# dualsmartplug.net
KiCad netlist of a schematic drawn in EAGLE
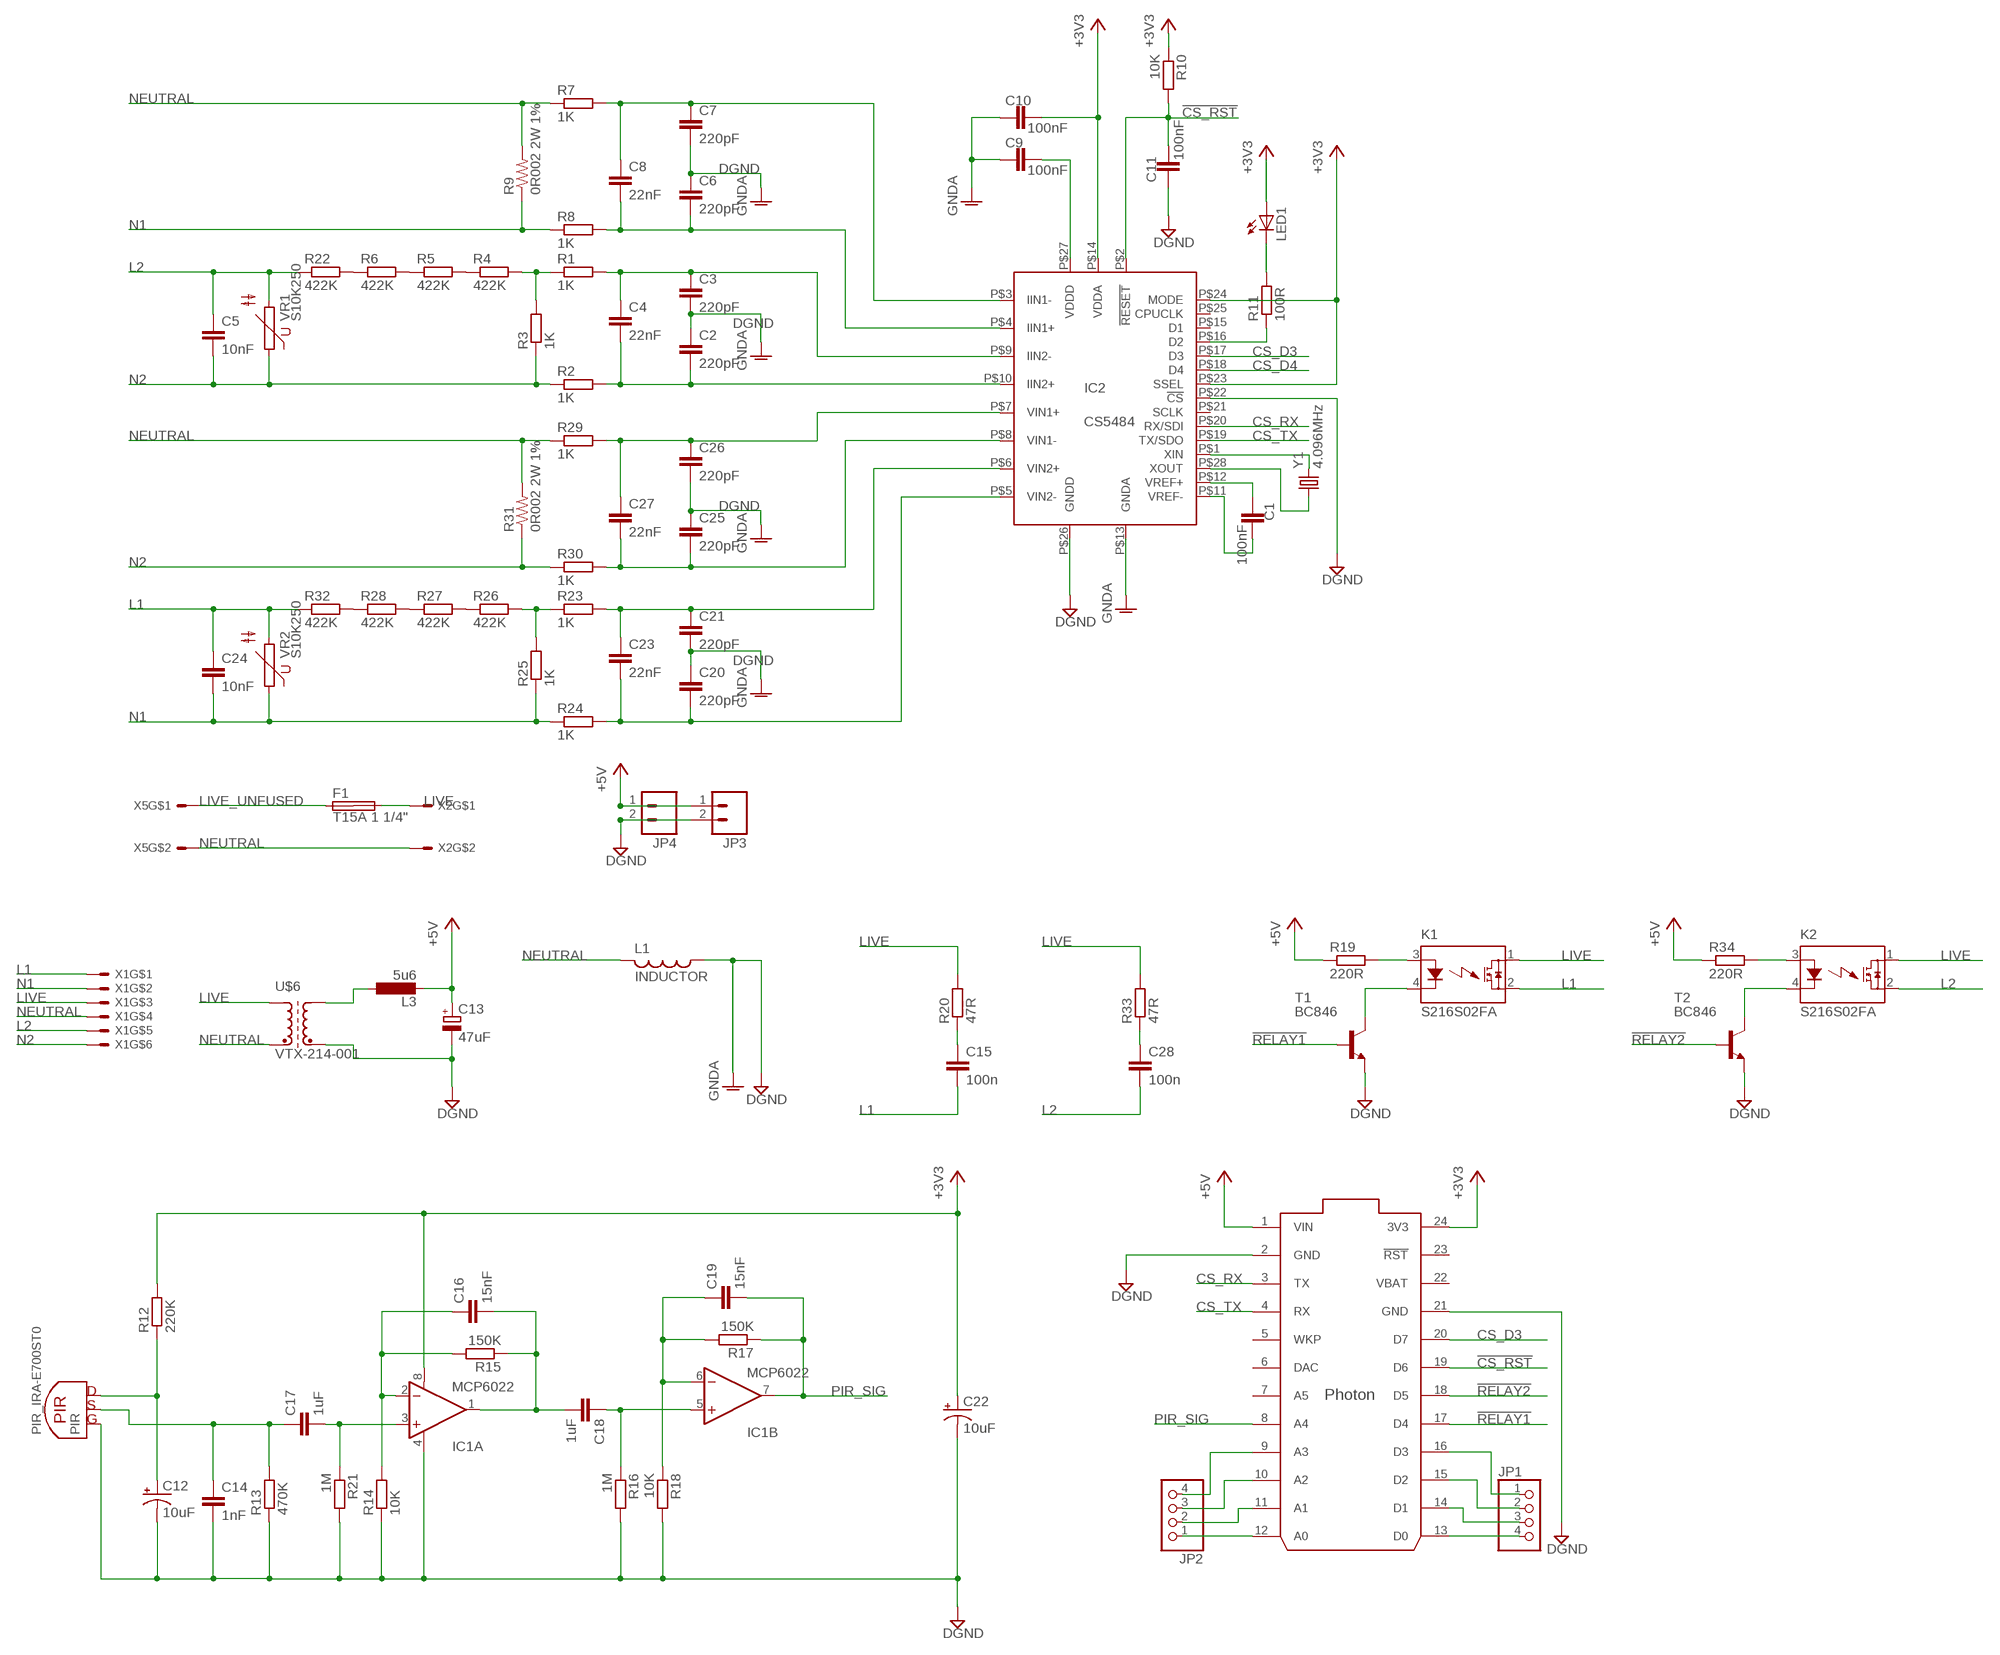
[diagram p0: schematic, sheet 1]

(export (version "E")
  (design (tool "Eeschema 10.0.6"))
  (components
    (comp (ref "C1")
      (value "100nF")
      (footprint "eagle-import:0603-CAP")
      (libsource (lib "eagle-import") (part "CAP0603-CAP"))
    )
    (comp (ref "C2")
      (value "220pF")
      (footprint "eagle-import:0603-CAP")
      (libsource (lib "eagle-import") (part "CAP0603-CAP"))
    )
    (comp (ref "C3")
      (value "220pF")
      (footprint "eagle-import:0603-CAP")
      (libsource (lib "eagle-import") (part "CAP0603-CAP"))
    )
    (comp (ref "C4")
      (value "22nF")
      (footprint "eagle-import:0603-CAP")
      (libsource (lib "eagle-import") (part "CAP0603-CAP"))
    )
    (comp (ref "C5")
      (value "10nF")
      (footprint "eagle-import:0603-CAP")
      (libsource (lib "eagle-import") (part "CAP0603-CAP"))
    )
    (comp (ref "C6")
      (value "220pF")
      (footprint "eagle-import:0603-CAP")
      (libsource (lib "eagle-import") (part "CAP0603-CAP"))
    )
    (comp (ref "C7")
      (value "220pF")
      (footprint "eagle-import:0603-CAP")
      (libsource (lib "eagle-import") (part "CAP0603-CAP"))
    )
    (comp (ref "C8")
      (value "22nF")
      (footprint "eagle-import:0603-CAP")
      (libsource (lib "eagle-import") (part "CAP0603-CAP"))
    )
    (comp (ref "C9")
      (value "100nF")
      (footprint "eagle-import:0603-CAP")
      (libsource (lib "eagle-import") (part "CAP0603-CAP"))
    )
    (comp (ref "C10")
      (value "100nF")
      (footprint "eagle-import:0603-CAP")
      (libsource (lib "eagle-import") (part "CAP0603-CAP"))
    )
    (comp (ref "C11")
      (value "100nF")
      (footprint "eagle-import:0603-CAP")
      (libsource (lib "eagle-import") (part "CAP0603-CAP"))
    )
    (comp (ref "C12")
      (value "10uF")
      (footprint "eagle-import:EIA3216")
      (libsource (lib "eagle-import") (part "CAP_POL1206"))
    )
    (comp (ref "C13")
      (value "47uF")
      (footprint "eagle-import:153CLV-0505")
      (libsource (lib "eagle-import") (part "CPOL-EU153CLV-0505"))
    )
    (comp (ref "C14")
      (value "1nF")
      (footprint "eagle-import:0603-CAP")
      (libsource (lib "eagle-import") (part "smartplug_CAP0603-CAP"))
    )
    (comp (ref "C15")
      (value "100n")
      (footprint "eagle-import:C150-054X183")
      (libsource (lib "eagle-import") (part "C-EU150-054X183"))
    )
    (comp (ref "C16")
      (value "15nF")
      (footprint "eagle-import:0603-CAP")
      (libsource (lib "eagle-import") (part "smartplug_CAP0603-CAP"))
    )
    (comp (ref "C17")
      (value "1uF")
      (footprint "eagle-import:0603-CAP")
      (libsource (lib "eagle-import") (part "smartplug_CAP0603-CAP"))
    )
    (comp (ref "C18")
      (value "1uF")
      (footprint "eagle-import:0603-CAP")
      (libsource (lib "eagle-import") (part "smartplug_CAP0603-CAP"))
    )
    (comp (ref "C19")
      (value "15nF")
      (footprint "eagle-import:0603-CAP")
      (libsource (lib "eagle-import") (part "smartplug_CAP0603-CAP"))
    )
    (comp (ref "C20")
      (value "220pF")
      (footprint "eagle-import:0603-CAP")
      (libsource (lib "eagle-import") (part "CAP0603-CAP"))
    )
    (comp (ref "C21")
      (value "220pF")
      (footprint "eagle-import:0603-CAP")
      (libsource (lib "eagle-import") (part "CAP0603-CAP"))
    )
    (comp (ref "C22")
      (value "10uF")
      (footprint "eagle-import:EIA3216")
      (libsource (lib "eagle-import") (part "CAP_POL1206"))
    )
    (comp (ref "C23")
      (value "22nF")
      (footprint "eagle-import:0603-CAP")
      (libsource (lib "eagle-import") (part "CAP0603-CAP"))
    )
    (comp (ref "C24")
      (value "10nF")
      (footprint "eagle-import:0603-CAP")
      (libsource (lib "eagle-import") (part "CAP0603-CAP"))
    )
    (comp (ref "C25")
      (value "220pF")
      (footprint "eagle-import:0603-CAP")
      (libsource (lib "eagle-import") (part "CAP0603-CAP"))
    )
    (comp (ref "C26")
      (value "220pF")
      (footprint "eagle-import:0603-CAP")
      (libsource (lib "eagle-import") (part "CAP0603-CAP"))
    )
    (comp (ref "C27")
      (value "22nF")
      (footprint "eagle-import:0603-CAP")
      (libsource (lib "eagle-import") (part "CAP0603-CAP"))
    )
    (comp (ref "C28")
      (value "100n")
      (footprint "eagle-import:C150-054X183")
      (libsource (lib "eagle-import") (part "C-EU150-054X183"))
    )
    (comp (ref "F1")
      (value "T15A 1 1/4\"")
      (footprint "eagle-import:SHURTER")
      (fields (field (name "MPN") "0031.8231"))
      (libsource (lib "eagle-import") (part "SHURTER_0031.8231"))
    )
    (comp (ref "IC1")
      (value "MCP6022")
      (footprint "eagle-import:SO08")
      (libsource (lib "eagle-import") (part "OPAMP-DUALU"))
    )
    (comp (ref "IC2")
      (value "CS5484")
      (footprint "eagle-import:QFN28-5X5")
      (libsource (lib "eagle-import") (part "CS5484"))
    )
    (comp (ref "JP1")
      (value "PINHD-1X4")
      (footprint "eagle-import:1X04")
      (libsource (lib "eagle-import") (part "PINHD-1X4"))
    )
    (comp (ref "JP2")
      (value "PINHD-1X4")
      (footprint "eagle-import:1X04")
      (libsource (lib "eagle-import") (part "PINHD-1X4"))
    )
    (comp (ref "JP3")
      (value "M02PTH")
      (footprint "eagle-import:1X02")
      (libsource (lib "eagle-import") (part "M02PTH"))
    )
    (comp (ref "JP4")
      (value "M02PTH")
      (footprint "eagle-import:1X02")
      (libsource (lib "eagle-import") (part "M02PTH"))
    )
    (comp (ref "K1")
      (value "S216S02FA")
      (footprint "eagle-import:S216S02F")
      (fields (field (name "MANUF_PART#") "S216S02F"))
      (libsource (lib "eagle-import") (part "S216S02FA"))
    )
    (comp (ref "K2")
      (value "S216S02FA")
      (footprint "eagle-import:S216S02F")
      (fields (field (name "MANUF_PART#") "S216S02F"))
      (libsource (lib "eagle-import") (part "S216S02FA"))
    )
    (comp (ref "L1")
      (value "INDUCTOR")
      (footprint "eagle-import:0603")
      (libsource (lib "eagle-import") (part "INDUCTOR"))
    )
    (comp (ref "L3")
      (value "5u6")
      (footprint "eagle-import:ELLCTP")
      (libsource (lib "eagle-import") (part "ELLCTP"))
    )
    (comp (ref "LED1")
      (value "LEDCHIPLED_1206")
      (footprint "eagle-import:CHIPLED_1206")
      (libsource (lib "eagle-import") (part "LEDCHIPLED_1206"))
    )
    (comp (ref "PIR")
      (value "PIR_IRA-E700ST0")
      (footprint "eagle-import:PIR_IRA-E700ST0")
      (libsource (lib "eagle-import") (part "PIR_IRA-E700ST0"))
    )
    (comp (ref "R1")
      (value "1K")
      (footprint "eagle-import:0603")
      (libsource (lib "eagle-import") (part "R-EU_0603"))
    )
    (comp (ref "R2")
      (value "1K")
      (footprint "eagle-import:0603")
      (libsource (lib "eagle-import") (part "R-EU_0603"))
    )
    (comp (ref "R3")
      (value "1K")
      (footprint "eagle-import:0603")
      (libsource (lib "eagle-import") (part "R-EU_0603"))
    )
    (comp (ref "R4")
      (value "422K")
      (footprint "eagle-import:0603")
      (libsource (lib "eagle-import") (part "R-EU_0603"))
    )
    (comp (ref "R5")
      (value "422K")
      (footprint "eagle-import:0603")
      (libsource (lib "eagle-import") (part "R-EU_0603"))
    )
    (comp (ref "R6")
      (value "422K")
      (footprint "eagle-import:0603")
      (libsource (lib "eagle-import") (part "R-EU_0603"))
    )
    (comp (ref "R7")
      (value "1K")
      (footprint "eagle-import:0603")
      (libsource (lib "eagle-import") (part "R-EU_0603"))
    )
    (comp (ref "R8")
      (value "1K")
      (footprint "eagle-import:0603")
      (libsource (lib "eagle-import") (part "R-EU_0603"))
    )
    (comp (ref "R9")
      (value "0R002 2W 1%")
      (footprint "eagle-import:R2512")
      (fields (field (name "MANUF_PART#") "CRF2512-FV-R002ELF"))
      (libsource (lib "eagle-import") (part "RESISTOR2512"))
    )
    (comp (ref "R10")
      (value "10K")
      (footprint "eagle-import:0603")
      (libsource (lib "eagle-import") (part "R-EU_0603"))
    )
    (comp (ref "R11")
      (value "100R")
      (footprint "eagle-import:0603")
      (libsource (lib "eagle-import") (part "R-EU_0603"))
    )
    (comp (ref "R12")
      (value "220K")
      (footprint "eagle-import:0603")
      (libsource (lib "eagle-import") (part "R-EU_0603"))
    )
    (comp (ref "R13")
      (value "470K")
      (footprint "eagle-import:0603")
      (libsource (lib "eagle-import") (part "R-EU_0603"))
    )
    (comp (ref "R14")
      (value "10K")
      (footprint "eagle-import:0603")
      (libsource (lib "eagle-import") (part "R-EU_0603"))
    )
    (comp (ref "R15")
      (value "150K")
      (footprint "eagle-import:0603")
      (libsource (lib "eagle-import") (part "R-EU_0603"))
    )
    (comp (ref "R16")
      (value "1M")
      (footprint "eagle-import:0603")
      (libsource (lib "eagle-import") (part "R-EU_0603"))
    )
    (comp (ref "R17")
      (value "150K")
      (footprint "eagle-import:0603")
      (libsource (lib "eagle-import") (part "R-EU_0603"))
    )
    (comp (ref "R18")
      (value "10K")
      (footprint "eagle-import:0603")
      (libsource (lib "eagle-import") (part "R-EU_0603"))
    )
    (comp (ref "R19")
      (value "220R")
      (footprint "eagle-import:0603")
      (libsource (lib "eagle-import") (part "R-EU_0603"))
    )
    (comp (ref "R20")
      (value "47R")
      (footprint "eagle-import:0617V")
      (libsource (lib "eagle-import") (part "R-EU_0617/5V"))
    )
    (comp (ref "R21")
      (value "1M")
      (footprint "eagle-import:0603")
      (libsource (lib "eagle-import") (part "R-EU_0603"))
    )
    (comp (ref "R22")
      (value "422K")
      (footprint "eagle-import:0603")
      (libsource (lib "eagle-import") (part "R-EU_0603"))
    )
    (comp (ref "R23")
      (value "1K")
      (footprint "eagle-import:0603")
      (libsource (lib "eagle-import") (part "R-EU_0603"))
    )
    (comp (ref "R24")
      (value "1K")
      (footprint "eagle-import:0603")
      (libsource (lib "eagle-import") (part "R-EU_0603"))
    )
    (comp (ref "R25")
      (value "1K")
      (footprint "eagle-import:0603")
      (libsource (lib "eagle-import") (part "R-EU_0603"))
    )
    (comp (ref "R26")
      (value "422K")
      (footprint "eagle-import:0603")
      (libsource (lib "eagle-import") (part "R-EU_0603"))
    )
    (comp (ref "R27")
      (value "422K")
      (footprint "eagle-import:0603")
      (libsource (lib "eagle-import") (part "R-EU_0603"))
    )
    (comp (ref "R28")
      (value "422K")
      (footprint "eagle-import:0603")
      (libsource (lib "eagle-import") (part "R-EU_0603"))
    )
    (comp (ref "R29")
      (value "1K")
      (footprint "eagle-import:0603")
      (libsource (lib "eagle-import") (part "R-EU_0603"))
    )
    (comp (ref "R30")
      (value "1K")
      (footprint "eagle-import:0603")
      (libsource (lib "eagle-import") (part "R-EU_0603"))
    )
    (comp (ref "R31")
      (value "0R002 2W 1%")
      (footprint "eagle-import:R2512")
      (fields (field (name "MANUF_PART#") "CRF2512-FV-R002ELF"))
      (libsource (lib "eagle-import") (part "RESISTOR2512"))
    )
    (comp (ref "R32")
      (value "422K")
      (footprint "eagle-import:0603")
      (libsource (lib "eagle-import") (part "R-EU_0603"))
    )
    (comp (ref "R33")
      (value "47R")
      (footprint "eagle-import:0617V")
      (libsource (lib "eagle-import") (part "R-EU_0617/5V"))
    )
    (comp (ref "R34")
      (value "220R")
      (footprint "eagle-import:0603")
      (libsource (lib "eagle-import") (part "R-EU_0603"))
    )
    (comp (ref "T1")
      (value "BC846")
      (footprint "eagle-import:SOT23")
      (libsource (lib "eagle-import") (part "BC846"))
    )
    (comp (ref "T2")
      (value "BC846")
      (footprint "eagle-import:SOT23")
      (libsource (lib "eagle-import") (part "BC846"))
    )
    (comp (ref "U$2")
      (value "PHOTON_WITH_HEADERS")
      (footprint "eagle-import:PHOTON")
      (libsource (lib "eagle-import") (part "PHOTON_WITH_HEADERS"))
    )
    (comp (ref "U$6")
      (value "VTX-214-001")
      (footprint "eagle-import:VTX-214-001")
      (libsource (lib "eagle-import") (part "VTX-214-001"))
    )
    (comp (ref "VR1")
      (value "S10K250")
      (footprint "eagle-import:S10K250")
      (fields (field (name "MANUF_PART#") "B72210S0251K101"))
      (libsource (lib "eagle-import") (part "S10K250"))
    )
    (comp (ref "VR2")
      (value "S10K250")
      (footprint "eagle-import:S10K250")
      (fields (field (name "MANUF_PART#") "B72210S0251K101"))
      (libsource (lib "eagle-import") (part "S10K250"))
    )
    (comp (ref "X1")
      (value "MOLEX-39357-6")
      (footprint "eagle-import:MOLEX-39357-6")
      (libsource (lib "eagle-import") (part "MOLEX-39357-6"))
    )
    (comp (ref "X2")
      (value "MOLEX-39357-2")
      (footprint "eagle-import:MOLEX-39357")
      (libsource (lib "eagle-import") (part "MOLEX-39357-2"))
    )
    (comp (ref "X5")
      (value "MOLEX-39357-2")
      (footprint "eagle-import:MOLEX-39357")
      (libsource (lib "eagle-import") (part "MOLEX-39357-2"))
    )
    (comp (ref "Y1")
      (value "4.096MHz")
      (footprint "eagle-import:CRYSTAL-SMD-10.5X4.8-2PIN")
      (fields (field (name "MANUF_PART#") "ABLS2-4.096MHZ-D4Y-T"))
      (libsource (lib "eagle-import") (part "CRYSTAL10.5X4.8"))
    )
  )
  (nets
    (net (code "1") (name "+3V3") (class "Default")
      (node (ref "C10") (pin "2") (pinfunction "2_2") (pintype "passive"))
      (node (ref "C22") (pin "A") (pinfunction "+_A") (pintype "passive"))
      (node (ref "IC1") (pin "8") (pinfunction "V+_8") (pintype "power_in"))
      (node (ref "IC2") (pin "P$14") (pinfunction "VDDA_P$14") (pintype "input"))
      (node (ref "IC2") (pin "P$23") (pinfunction "SSEL_P$23") (pintype "output"))
      (node (ref "IC2") (pin "P$24") (pinfunction "MODE_P$24") (pintype "input"))
      (node (ref "LED1") (pin "A") (pinfunction "A_A") (pintype "passive"))
      (node (ref "R10") (pin "1") (pinfunction "1_1") (pintype "passive"))
      (node (ref "R12") (pin "2") (pinfunction "2_2") (pintype "passive"))
      (node (ref "U$2") (pin "24") (pinfunction "3V3_24") (pintype "power_in"))
    )
    (net (code "2") (name "+5V") (class "Default")
      (node (ref "C13") (pin "+") (pinfunction "+_+") (pintype "passive"))
      (node (ref "JP3") (pin "1") (pinfunction "1_1") (pintype "passive"))
      (node (ref "JP4") (pin "1") (pinfunction "1_1") (pintype "passive"))
      (node (ref "L3") (pin "2") (pinfunction "2_2") (pintype "passive"))
      (node (ref "R19") (pin "1") (pinfunction "1_1") (pintype "passive"))
      (node (ref "R34") (pin "1") (pinfunction "1_1") (pintype "passive"))
      (node (ref "U$2") (pin "1") (pinfunction "VIN_1") (pintype "power_in"))
    )
    (net (code "3") (name "/CS_D3") (class "Default")
      (node (ref "IC2") (pin "P$17") (pinfunction "D3_P$17") (pintype "output"))
      (node (ref "U$2") (pin "20") (pinfunction "D7_20") (pintype "bidirectional"))
    )
    (net (code "4") (name "/CS_D4") (class "Default")
      (node (ref "IC2") (pin "P$18") (pinfunction "D4_P$18") (pintype "output"))
    )
    (net (code "5") (name "/CS_RX") (class "Default")
      (node (ref "IC2") (pin "P$20") (pinfunction "RX/SDI_P$20") (pintype "input"))
      (node (ref "U$2") (pin "3") (pinfunction "TX_3") (pintype "bidirectional"))
    )
    (net (code "6") (name "/CS_TX") (class "Default")
      (node (ref "IC2") (pin "P$19") (pinfunction "TX/SDO_P$19") (pintype "output"))
      (node (ref "U$2") (pin "4") (pinfunction "RX_4") (pintype "bidirectional"))
    )
    (net (code "7") (name "/L1") (class "Default")
      (node (ref "C15") (pin "2") (pinfunction "2_2") (pintype "passive"))
      (node (ref "C24") (pin "1") (pinfunction "1_1") (pintype "passive"))
      (node (ref "K1") (pin "2") (pinfunction "DS2_2") (pintype "passive"))
      (node (ref "R32") (pin "1") (pinfunction "1_1") (pintype "passive"))
      (node (ref "VR2") (pin "2") (pinfunction "2_2") (pintype "passive"))
      (node (ref "X1") (pin "P$1") (pinfunction "S_P$1") (pintype "passive"))
    )
    (net (code "8") (name "/L2") (class "Default")
      (node (ref "C28") (pin "2") (pinfunction "2_2") (pintype "passive"))
      (node (ref "C5") (pin "1") (pinfunction "1_1") (pintype "passive"))
      (node (ref "K2") (pin "2") (pinfunction "DS2_2") (pintype "passive"))
      (node (ref "R22") (pin "1") (pinfunction "1_1") (pintype "passive"))
      (node (ref "VR1") (pin "2") (pinfunction "2_2") (pintype "passive"))
      (node (ref "X1") (pin "P$5") (pinfunction "S_P$5") (pintype "passive"))
    )
    (net (code "9") (name "/LIVE") (class "Default")
      (node (ref "F1") (pin "P$7") (pinfunction "2A_P$7") (pintype "passive"))
      (node (ref "K1") (pin "1") (pinfunction "DS1_1") (pintype "passive"))
      (node (ref "K2") (pin "1") (pinfunction "DS1_1") (pintype "passive"))
      (node (ref "R20") (pin "2") (pinfunction "2_2") (pintype "passive"))
      (node (ref "R33") (pin "2") (pinfunction "2_2") (pintype "passive"))
      (node (ref "U$6") (pin "P$L") (pinfunction "A1_P$L") (pintype "passive"))
      (node (ref "X1") (pin "P$3") (pinfunction "S_P$3") (pintype "passive"))
      (node (ref "X2") (pin "P$1") (pinfunction "S_P$1") (pintype "passive"))
    )
    (net (code "10") (name "/LIVE_UNFUSED") (class "Default")
      (node (ref "F1") (pin "P$5") (pinfunction "1A_P$5") (pintype "passive"))
      (node (ref "X5") (pin "P$1") (pinfunction "S_P$1") (pintype "passive"))
    )
    (net (code "11") (name "/N1") (class "Default")
      (node (ref "C24") (pin "2") (pinfunction "2_2") (pintype "passive"))
      (node (ref "R24") (pin "1") (pinfunction "1_1") (pintype "passive"))
      (node (ref "R25") (pin "1") (pinfunction "1_1") (pintype "passive"))
      (node (ref "R8") (pin "1") (pinfunction "1_1") (pintype "passive"))
      (node (ref "R9") (pin "1") (pinfunction "1_1") (pintype "passive"))
      (node (ref "VR2") (pin "1") (pinfunction "1_1") (pintype "passive"))
      (node (ref "X1") (pin "P$2") (pinfunction "S_P$2") (pintype "passive"))
    )
    (net (code "12") (name "/N2") (class "Default")
      (node (ref "C5") (pin "2") (pinfunction "2_2") (pintype "passive"))
      (node (ref "R2") (pin "1") (pinfunction "1_1") (pintype "passive"))
      (node (ref "R3") (pin "1") (pinfunction "1_1") (pintype "passive"))
      (node (ref "R30") (pin "1") (pinfunction "1_1") (pintype "passive"))
      (node (ref "R31") (pin "1") (pinfunction "1_1") (pintype "passive"))
      (node (ref "VR1") (pin "1") (pinfunction "1_1") (pintype "passive"))
      (node (ref "X1") (pin "P$6") (pinfunction "S_P$6") (pintype "passive"))
    )
    (net (code "13") (name "/NEUTRAL") (class "Default")
      (node (ref "L1") (pin "2") (pinfunction "2_2") (pintype "passive"))
      (node (ref "R29") (pin "1") (pinfunction "1_1") (pintype "passive"))
      (node (ref "R31") (pin "2") (pinfunction "2_2") (pintype "passive"))
      (node (ref "R7") (pin "1") (pinfunction "1_1") (pintype "passive"))
      (node (ref "R9") (pin "2") (pinfunction "2_2") (pintype "passive"))
      (node (ref "U$6") (pin "P$N") (pinfunction "E1_P$N") (pintype "passive"))
      (node (ref "X1") (pin "P$4") (pinfunction "S_P$4") (pintype "passive"))
      (node (ref "X2") (pin "P$2") (pinfunction "S_P$2") (pintype "passive"))
      (node (ref "X5") (pin "P$2") (pinfunction "S_P$2") (pintype "passive"))
    )
    (net (code "14") (name "/PIR_SIG") (class "Default")
      (node (ref "C19") (pin "2") (pinfunction "2_2") (pintype "passive"))
      (node (ref "IC1") (pin "7") (pinfunction "OUT_7") (pintype "output"))
      (node (ref "R17") (pin "1") (pinfunction "1_1") (pintype "passive"))
      (node (ref "U$2") (pin "8") (pinfunction "A4_8") (pintype "bidirectional"))
    )
    (net (code "15") (name "/VBAT") (class "Default")
      (node (ref "U$2") (pin "22") (pinfunction "VBAT_22") (pintype "power_in"))
    )
    (net (code "16") (name "/~{CS_RST}") (class "Default")
      (node (ref "C11") (pin "2") (pinfunction "2_2") (pintype "passive"))
      (node (ref "IC2") (pin "P$2") (pinfunction "~{RESET}_P$2") (pintype "input"))
      (node (ref "R10") (pin "2") (pinfunction "2_2") (pintype "passive"))
      (node (ref "U$2") (pin "19") (pinfunction "D6_19") (pintype "bidirectional"))
    )
    (net (code "17") (name "/~{RELAY1}") (class "Default")
      (node (ref "T1") (pin "1") (pinfunction "B_1") (pintype "passive"))
      (node (ref "U$2") (pin "17") (pinfunction "D4_17") (pintype "bidirectional"))
    )
    (net (code "18") (name "/~{RELAY2}") (class "Default")
      (node (ref "T2") (pin "1") (pinfunction "B_1") (pintype "passive"))
      (node (ref "U$2") (pin "18") (pinfunction "D5_18") (pintype "bidirectional"))
    )
    (net (code "19") (name "DGND") (class "Default")
      (node (ref "C10") (pin "1") (pinfunction "1_1") (pintype "passive"))
      (node (ref "C11") (pin "1") (pinfunction "1_1") (pintype "passive"))
      (node (ref "C12") (pin "C") (pinfunction "-_C") (pintype "passive"))
      (node (ref "C13") (pin "-") (pinfunction "-_-") (pintype "passive"))
      (node (ref "C14") (pin "2") (pinfunction "2_2") (pintype "passive"))
      (node (ref "C2") (pin "1") (pinfunction "1_1") (pintype "passive"))
      (node (ref "C20") (pin "1") (pinfunction "1_1") (pintype "passive"))
      (node (ref "C21") (pin "2") (pinfunction "2_2") (pintype "passive"))
      (node (ref "C22") (pin "C") (pinfunction "-_C") (pintype "passive"))
      (node (ref "C25") (pin "1") (pinfunction "1_1") (pintype "passive"))
      (node (ref "C26") (pin "2") (pinfunction "2_2") (pintype "passive"))
      (node (ref "C3") (pin "2") (pinfunction "2_2") (pintype "passive"))
      (node (ref "C6") (pin "1") (pinfunction "1_1") (pintype "passive"))
      (node (ref "C7") (pin "2") (pinfunction "2_2") (pintype "passive"))
      (node (ref "C9") (pin "1") (pinfunction "1_1") (pintype "passive"))
      (node (ref "IC1") (pin "4") (pinfunction "V-_4") (pintype "power_in"))
      (node (ref "IC2") (pin "P$13") (pinfunction "GNDA_P$13") (pintype "power_in"))
      (node (ref "IC2") (pin "P$22") (pinfunction "~{CS}_P$22") (pintype "output"))
      (node (ref "IC2") (pin "P$26") (pinfunction "GNDD_P$26") (pintype "bidirectional"))
      (node (ref "JP3") (pin "2") (pinfunction "2_2") (pintype "passive"))
      (node (ref "JP4") (pin "2") (pinfunction "2_2") (pintype "passive"))
      (node (ref "L1") (pin "1") (pinfunction "1_1") (pintype "passive"))
      (node (ref "PIR") (pin "GND") (pinfunction "GND_GND") (pintype "power_in"))
      (node (ref "R13") (pin "1") (pinfunction "1_1") (pintype "passive"))
      (node (ref "R14") (pin "1") (pinfunction "1_1") (pintype "passive"))
      (node (ref "R16") (pin "2") (pinfunction "2_2") (pintype "passive"))
      (node (ref "R18") (pin "2") (pinfunction "2_2") (pintype "passive"))
      (node (ref "R21") (pin "2") (pinfunction "2_2") (pintype "passive"))
      (node (ref "T1") (pin "2") (pinfunction "E_2") (pintype "passive"))
      (node (ref "T2") (pin "2") (pinfunction "E_2") (pintype "passive"))
      (node (ref "U$2") (pin "2") (pinfunction "GND_2") (pintype "power_in"))
      (node (ref "U$2") (pin "21") (pinfunction "GND_21") (pintype "power_in"))
      (node (ref "U$6") (pin "P$V-") (pinfunction "E2_P$V-") (pintype "passive"))
    )
    (net (code "20") (name "Net-(C12-+)") (class "Default")
      (node (ref "C12") (pin "A") (pinfunction "+_A") (pintype "passive"))
      (node (ref "PIR") (pin "DRAIN+") (pinfunction "DRAIN_DRAIN+") (pintype "passive"))
      (node (ref "R12") (pin "1") (pinfunction "1_1") (pintype "passive"))
    )
    (net (code "21") (name "Net-(C14-Pad1)") (class "Default")
      (node (ref "C14") (pin "1") (pinfunction "1_1") (pintype "passive"))
      (node (ref "C17") (pin "1") (pinfunction "1_1") (pintype "passive"))
      (node (ref "PIR") (pin "SOURCE") (pinfunction "SOURCE_SOURCE") (pintype "output"))
      (node (ref "R13") (pin "2") (pinfunction "2_2") (pintype "passive"))
    )
    (net (code "22") (name "Net-(C15-Pad1)") (class "Default")
      (node (ref "C15") (pin "1") (pinfunction "1_1") (pintype "passive"))
      (node (ref "R20") (pin "1") (pinfunction "1_1") (pintype "passive"))
    )
    (net (code "23") (name "Net-(C28-Pad1)") (class "Default")
      (node (ref "C28") (pin "1") (pinfunction "1_1") (pintype "passive"))
      (node (ref "R33") (pin "1") (pinfunction "1_1") (pintype "passive"))
    )
    (net (code "24") (name "Net-(IC1A-+IN)") (class "Default")
      (node (ref "C17") (pin "2") (pinfunction "2_2") (pintype "passive"))
      (node (ref "IC1") (pin "3") (pinfunction "+IN_3") (pintype "input"))
      (node (ref "R21") (pin "1") (pinfunction "1_1") (pintype "passive"))
    )
    (net (code "25") (name "Net-(IC1A--IN)") (class "Default")
      (node (ref "C16") (pin "1") (pinfunction "1_1") (pintype "passive"))
      (node (ref "IC1") (pin "2") (pinfunction "-IN_2") (pintype "input"))
      (node (ref "R14") (pin "2") (pinfunction "2_2") (pintype "passive"))
      (node (ref "R15") (pin "2") (pinfunction "2_2") (pintype "passive"))
    )
    (net (code "26") (name "Net-(IC1A-OUT)") (class "Default")
      (node (ref "C16") (pin "2") (pinfunction "2_2") (pintype "passive"))
      (node (ref "C18") (pin "2") (pinfunction "2_2") (pintype "passive"))
      (node (ref "IC1") (pin "1") (pinfunction "OUT_1") (pintype "output"))
      (node (ref "R15") (pin "1") (pinfunction "1_1") (pintype "passive"))
    )
    (net (code "27") (name "Net-(IC1B-+IN)") (class "Default")
      (node (ref "C18") (pin "1") (pinfunction "1_1") (pintype "passive"))
      (node (ref "IC1") (pin "5") (pinfunction "+IN_5") (pintype "input"))
      (node (ref "R16") (pin "1") (pinfunction "1_1") (pintype "passive"))
    )
    (net (code "28") (name "Net-(IC1B--IN)") (class "Default")
      (node (ref "C19") (pin "1") (pinfunction "1_1") (pintype "passive"))
      (node (ref "IC1") (pin "6") (pinfunction "-IN_6") (pintype "input"))
      (node (ref "R17") (pin "2") (pinfunction "2_2") (pintype "passive"))
      (node (ref "R18") (pin "1") (pinfunction "1_1") (pintype "passive"))
    )
    (net (code "29") (name "Net-(IC2-D2)") (class "Default")
      (node (ref "IC2") (pin "P$16") (pinfunction "D2_P$16") (pintype "output"))
      (node (ref "R11") (pin "1") (pinfunction "1_1") (pintype "passive"))
    )
    (net (code "30") (name "Net-(IC2-IIN1+)") (class "Default")
      (node (ref "C6") (pin "2") (pinfunction "2_2") (pintype "passive"))
      (node (ref "C8") (pin "2") (pinfunction "2_2") (pintype "passive"))
      (node (ref "IC2") (pin "P$4") (pinfunction "IIN1+_P$4") (pintype "input"))
      (node (ref "R8") (pin "2") (pinfunction "2_2") (pintype "passive"))
    )
    (net (code "31") (name "Net-(IC2-IIN1-)") (class "Default")
      (node (ref "C7") (pin "1") (pinfunction "1_1") (pintype "passive"))
      (node (ref "C8") (pin "1") (pinfunction "1_1") (pintype "passive"))
      (node (ref "IC2") (pin "P$3") (pinfunction "IIN1-_P$3") (pintype "input"))
      (node (ref "R7") (pin "2") (pinfunction "2_2") (pintype "passive"))
    )
    (net (code "32") (name "Net-(IC2-IIN2+)") (class "Default")
      (node (ref "C2") (pin "2") (pinfunction "2_2") (pintype "passive"))
      (node (ref "C4") (pin "2") (pinfunction "2_2") (pintype "passive"))
      (node (ref "IC2") (pin "P$10") (pinfunction "IIN2+_P$10") (pintype "input"))
      (node (ref "R2") (pin "2") (pinfunction "2_2") (pintype "passive"))
    )
    (net (code "33") (name "Net-(IC2-IIN2-)") (class "Default")
      (node (ref "C3") (pin "1") (pinfunction "1_1") (pintype "passive"))
      (node (ref "C4") (pin "1") (pinfunction "1_1") (pintype "passive"))
      (node (ref "IC2") (pin "P$9") (pinfunction "IIN2-_P$9") (pintype "input"))
      (node (ref "R1") (pin "2") (pinfunction "2_2") (pintype "passive"))
    )
    (net (code "34") (name "Net-(IC2-VDDD)") (class "Default")
      (node (ref "C9") (pin "2") (pinfunction "2_2") (pintype "passive"))
      (node (ref "IC2") (pin "P$27") (pinfunction "VDDD_P$27") (pintype "power_in"))
    )
    (net (code "35") (name "Net-(IC2-VIN1+)") (class "Default")
      (node (ref "C26") (pin "1") (pinfunction "1_1") (pintype "passive"))
      (node (ref "C27") (pin "1") (pinfunction "1_1") (pintype "passive"))
      (node (ref "IC2") (pin "P$7") (pinfunction "VIN1+_P$7") (pintype "input"))
      (node (ref "R29") (pin "2") (pinfunction "2_2") (pintype "passive"))
    )
    (net (code "36") (name "Net-(IC2-VIN1-)") (class "Default")
      (node (ref "C25") (pin "2") (pinfunction "2_2") (pintype "passive"))
      (node (ref "C27") (pin "2") (pinfunction "2_2") (pintype "passive"))
      (node (ref "IC2") (pin "P$8") (pinfunction "VIN1-_P$8") (pintype "input"))
      (node (ref "R30") (pin "2") (pinfunction "2_2") (pintype "passive"))
    )
    (net (code "37") (name "Net-(IC2-VIN2+)") (class "Default")
      (node (ref "C21") (pin "1") (pinfunction "1_1") (pintype "passive"))
      (node (ref "C23") (pin "1") (pinfunction "1_1") (pintype "passive"))
      (node (ref "IC2") (pin "P$6") (pinfunction "VIN2+_P$6") (pintype "input"))
      (node (ref "R23") (pin "2") (pinfunction "2_2") (pintype "passive"))
    )
    (net (code "38") (name "Net-(IC2-VIN2-)") (class "Default")
      (node (ref "C20") (pin "2") (pinfunction "2_2") (pintype "passive"))
      (node (ref "C23") (pin "2") (pinfunction "2_2") (pintype "passive"))
      (node (ref "IC2") (pin "P$5") (pinfunction "VIN2-_P$5") (pintype "input"))
      (node (ref "R24") (pin "2") (pinfunction "2_2") (pintype "passive"))
    )
    (net (code "39") (name "Net-(IC2-VREF+)") (class "Default")
      (node (ref "C1") (pin "1") (pinfunction "1_1") (pintype "passive"))
      (node (ref "IC2") (pin "P$12") (pinfunction "VREF+_P$12") (pintype "output"))
    )
    (net (code "40") (name "Net-(IC2-VREF-)") (class "Default")
      (node (ref "C1") (pin "2") (pinfunction "2_2") (pintype "passive"))
      (node (ref "IC2") (pin "P$11") (pinfunction "VREF-_P$11") (pintype "input"))
    )
    (net (code "41") (name "Net-(IC2-XIN)") (class "Default")
      (node (ref "IC2") (pin "P$1") (pinfunction "XIN_P$1") (pintype "input"))
      (node (ref "Y1") (pin "P$2") (pinfunction "2_P$2") (pintype "passive"))
    )
    (net (code "42") (name "Net-(IC2-XOUT)") (class "Default")
      (node (ref "IC2") (pin "P$28") (pinfunction "XOUT_P$28") (pintype "output"))
      (node (ref "Y1") (pin "P$1") (pinfunction "1_P$1") (pintype "passive"))
    )
    (net (code "43") (name "Net-(K1-A)") (class "Default")
      (node (ref "K1") (pin "3") (pinfunction "A_3") (pintype "passive"))
      (node (ref "R19") (pin "2") (pinfunction "2_2") (pintype "passive"))
    )
    (net (code "44") (name "Net-(K1-K)") (class "Default")
      (node (ref "K1") (pin "4") (pinfunction "K_4") (pintype "passive"))
      (node (ref "T1") (pin "3") (pinfunction "C_3") (pintype "passive"))
    )
    (net (code "45") (name "Net-(K2-A)") (class "Default")
      (node (ref "K2") (pin "3") (pinfunction "A_3") (pintype "passive"))
      (node (ref "R34") (pin "2") (pinfunction "2_2") (pintype "passive"))
    )
    (net (code "46") (name "Net-(K2-K)") (class "Default")
      (node (ref "K2") (pin "4") (pinfunction "K_4") (pintype "passive"))
      (node (ref "T2") (pin "3") (pinfunction "C_3") (pintype "passive"))
    )
    (net (code "47") (name "Net-(LED1-PadC)") (class "Default")
      (node (ref "LED1") (pin "C") (pinfunction "C_C") (pintype "passive"))
      (node (ref "R11") (pin "2") (pinfunction "2_2") (pintype "passive"))
    )
    (net (code "48") (name "Net-(R1-Pad1)") (class "Default")
      (node (ref "R1") (pin "1") (pinfunction "1_1") (pintype "passive"))
      (node (ref "R3") (pin "2") (pinfunction "2_2") (pintype "passive"))
      (node (ref "R4") (pin "2") (pinfunction "2_2") (pintype "passive"))
    )
    (net (code "49") (name "Net-(R4-Pad1)") (class "Default")
      (node (ref "R4") (pin "1") (pinfunction "1_1") (pintype "passive"))
      (node (ref "R5") (pin "2") (pinfunction "2_2") (pintype "passive"))
    )
    (net (code "50") (name "Net-(R5-Pad1)") (class "Default")
      (node (ref "R5") (pin "1") (pinfunction "1_1") (pintype "passive"))
      (node (ref "R6") (pin "2") (pinfunction "2_2") (pintype "passive"))
    )
    (net (code "51") (name "Net-(R22-Pad2)") (class "Default")
      (node (ref "R22") (pin "2") (pinfunction "2_2") (pintype "passive"))
      (node (ref "R6") (pin "1") (pinfunction "1_1") (pintype "passive"))
    )
    (net (code "52") (name "Net-(R23-Pad1)") (class "Default")
      (node (ref "R23") (pin "1") (pinfunction "1_1") (pintype "passive"))
      (node (ref "R25") (pin "2") (pinfunction "2_2") (pintype "passive"))
      (node (ref "R26") (pin "2") (pinfunction "2_2") (pintype "passive"))
    )
    (net (code "53") (name "Net-(R26-Pad1)") (class "Default")
      (node (ref "R26") (pin "1") (pinfunction "1_1") (pintype "passive"))
      (node (ref "R27") (pin "2") (pinfunction "2_2") (pintype "passive"))
    )
    (net (code "54") (name "Net-(R27-Pad1)") (class "Default")
      (node (ref "R27") (pin "1") (pinfunction "1_1") (pintype "passive"))
      (node (ref "R28") (pin "2") (pinfunction "2_2") (pintype "passive"))
    )
    (net (code "55") (name "Net-(R28-Pad1)") (class "Default")
      (node (ref "R28") (pin "1") (pinfunction "1_1") (pintype "passive"))
      (node (ref "R32") (pin "2") (pinfunction "2_2") (pintype "passive"))
    )
    (net (code "56") (name "Net-(U$2-A0)") (class "Default")
      (node (ref "JP2") (pin "1") (pinfunction "1_1") (pintype "passive"))
      (node (ref "U$2") (pin "12") (pinfunction "A0_12") (pintype "bidirectional"))
    )
    (net (code "57") (name "Net-(U$2-A1)") (class "Default")
      (node (ref "JP2") (pin "2") (pinfunction "2_2") (pintype "passive"))
      (node (ref "U$2") (pin "11") (pinfunction "A1_11") (pintype "bidirectional"))
    )
    (net (code "58") (name "Net-(U$2-A2)") (class "Default")
      (node (ref "JP2") (pin "3") (pinfunction "3_3") (pintype "passive"))
      (node (ref "U$2") (pin "10") (pinfunction "A2_10") (pintype "bidirectional"))
    )
    (net (code "59") (name "Net-(U$2-A3)") (class "Default")
      (node (ref "JP2") (pin "4") (pinfunction "4_4") (pintype "passive"))
      (node (ref "U$2") (pin "9") (pinfunction "A3_9") (pintype "bidirectional"))
    )
    (net (code "60") (name "Net-(U$2-D0)") (class "Default")
      (node (ref "JP1") (pin "4") (pinfunction "4_4") (pintype "passive"))
      (node (ref "U$2") (pin "13") (pinfunction "D0_13") (pintype "bidirectional"))
    )
    (net (code "61") (name "Net-(U$2-D1)") (class "Default")
      (node (ref "JP1") (pin "3") (pinfunction "3_3") (pintype "passive"))
      (node (ref "U$2") (pin "14") (pinfunction "D1_14") (pintype "bidirectional"))
    )
    (net (code "62") (name "Net-(U$2-D2)") (class "Default")
      (node (ref "JP1") (pin "2") (pinfunction "2_2") (pintype "passive"))
      (node (ref "U$2") (pin "15") (pinfunction "D2_15") (pintype "bidirectional"))
    )
    (net (code "63") (name "Net-(U$2-D3)") (class "Default")
      (node (ref "JP1") (pin "1") (pinfunction "1_1") (pintype "passive"))
      (node (ref "U$2") (pin "16") (pinfunction "D3_16") (pintype "bidirectional"))
    )
    (net (code "64") (name "Net-(U$6-A2)") (class "Default")
      (node (ref "L3") (pin "1") (pinfunction "1_1") (pintype "passive"))
      (node (ref "U$6") (pin "P$V+") (pinfunction "A2_P$V+") (pintype "passive"))
    )
    (net (code "65") (name "unconnected-(F1-1B-PadP$6)") (class "Default")
      (node (ref "F1") (pin "P$6") (pinfunction "1B_P$6") (pintype "passive"))
    )
    (net (code "66") (name "unconnected-(F1-2B-PadP$8)") (class "Default")
      (node (ref "F1") (pin "P$8") (pinfunction "2B_P$8") (pintype "passive"))
    )
    (net (code "67") (name "unconnected-(IC2-CPUCLK-PadP$25)") (class "Default")
      (node (ref "IC2") (pin "P$25") (pinfunction "CPUCLK_P$25") (pintype "output"))
    )
    (net (code "68") (name "unconnected-(IC2-D1-PadP$15)") (class "Default")
      (node (ref "IC2") (pin "P$15") (pinfunction "D1_P$15") (pintype "output"))
    )
    (net (code "69") (name "unconnected-(IC2-SCLK-PadP$21)") (class "Default")
      (node (ref "IC2") (pin "P$21") (pinfunction "SCLK_P$21") (pintype "output"))
    )
    (net (code "70") (name "unconnected-(U$2-A5-Pad7)") (class "Default")
      (node (ref "U$2") (pin "7") (pinfunction "A5_7") (pintype "bidirectional"))
    )
    (net (code "71") (name "unconnected-(U$2-DAC-Pad6)") (class "Default")
      (node (ref "U$2") (pin "6") (pinfunction "DAC_6") (pintype "bidirectional"))
    )
    (net (code "72") (name "unconnected-(U$2-WKP-Pad5)") (class "Default")
      (node (ref "U$2") (pin "5") (pinfunction "WKP_5") (pintype "bidirectional"))
    )
    (net (code "73") (name "unconnected-(U$2-~{RST}-Pad23)") (class "Default")
      (node (ref "U$2") (pin "23") (pinfunction "~{RST}_23") (pintype "bidirectional"))
    )
  )
)
